# CAP_BANK.net
KiCad netlist of a schematic drawn in Altium Designer
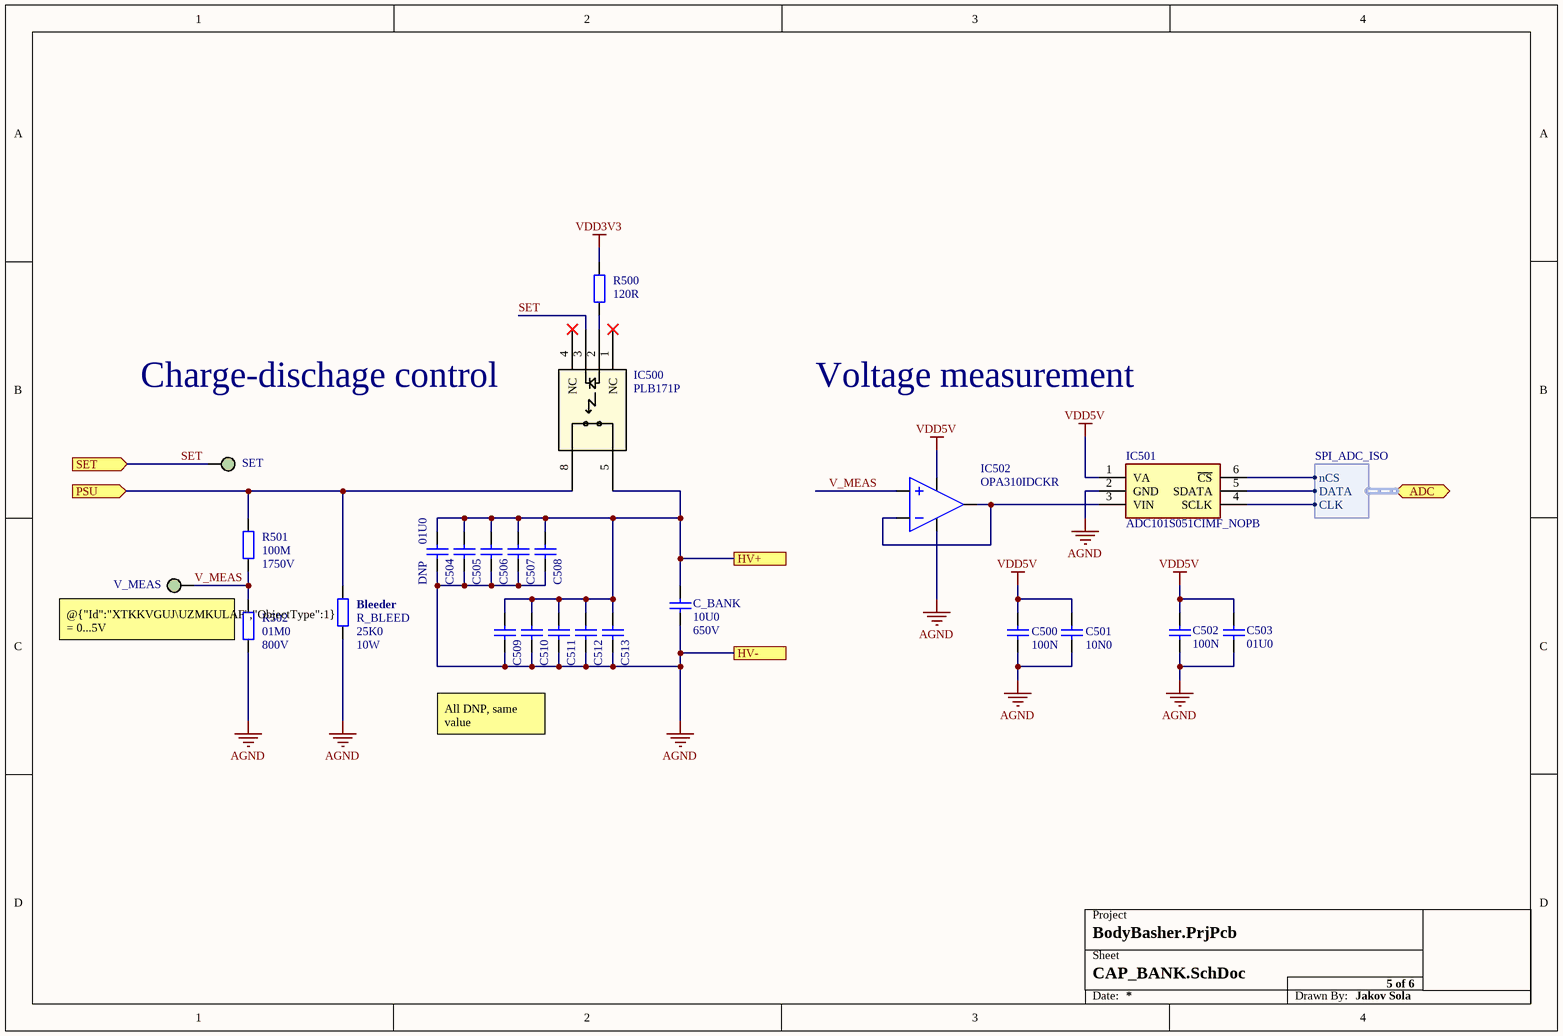
[diagram p0: CAP_BANK.SchDoc]

(export (version "E")
  (design (tool "Eeschema 10.0.6"))
  (components
    (comp (ref "C500")
      (value "Cap")
      (footprint "CAPC0603N")
      (fields
        (field (name "VALUE_4C") "100N")
        (field (name "VOLTAGE") "25V")
        (field (name "TOLERANCE") "0.1")
      )
      (libsource (lib "Capacitors") (part "Cap"))
    )
    (comp (ref "C501")
      (value "Cap")
      (footprint "CAPC0603N")
      (fields
        (field (name "VALUE_4C") "10N0")
        (field (name "VOLTAGE") "10V")
        (field (name "TOLERANCE") "0.1")
      )
      (libsource (lib "Capacitors") (part "Cap"))
    )
    (comp (ref "C502")
      (value "Cap")
      (footprint "CAPC0603N")
      (fields
        (field (name "VALUE_4C") "100N")
        (field (name "VOLTAGE") "25V")
        (field (name "TOLERANCE") "0.1")
      )
      (libsource (lib "Capacitors") (part "Cap"))
    )
    (comp (ref "C503")
      (value "Cap")
      (footprint "CAPC0603N")
      (fields
        (field (name "VALUE_4C") "01U0")
        (field (name "VOLTAGE") "25V")
        (field (name "TOLERANCE") "0.1")
      )
      (libsource (lib "Capacitors") (part "Cap"))
    )
    (comp (ref "C504")
      (value "Cap")
      (footprint "CAPC2220N")
      (fields
        (field (name "POPULATE") "DNP")
        (field (name "VALUE_4C") "01U0")
        (field (name "VOLTAGE") "600V")
        (field (name "TOLERANCE") "0.1")
      )
      (libsource (lib "Capacitors") (part "Cap"))
    )
    (comp (ref "C505")
      (value "Cap")
      (footprint "CAPC2220N")
      (fields (field (name "VOLTAGE") "600V") (field (name "TOLERANCE") "0.1"))
      (libsource (lib "Capacitors") (part "Cap"))
    )
    (comp (ref "C506")
      (value "Cap")
      (footprint "CAPC2220N")
      (fields (field (name "VOLTAGE") "600V") (field (name "TOLERANCE") "0.1"))
      (libsource (lib "Capacitors") (part "Cap"))
    )
    (comp (ref "C507")
      (value "Cap")
      (footprint "CAPC2220N")
      (fields (field (name "VOLTAGE") "600V") (field (name "TOLERANCE") "0.1"))
      (libsource (lib "Capacitors") (part "Cap"))
    )
    (comp (ref "C508")
      (value "Cap")
      (footprint "CAPC2220N")
      (fields (field (name "VOLTAGE") "600V") (field (name "TOLERANCE") "0.1"))
      (libsource (lib "Capacitors") (part "Cap"))
    )
    (comp (ref "C509")
      (value "Cap")
      (footprint "CAPC2220N")
      (fields (field (name "VOLTAGE") "600V") (field (name "TOLERANCE") "0.1"))
      (libsource (lib "Capacitors") (part "Cap"))
    )
    (comp (ref "C510")
      (value "Cap")
      (footprint "CAPC2220N")
      (fields (field (name "VOLTAGE") "600V") (field (name "TOLERANCE") "0.1"))
      (libsource (lib "Capacitors") (part "Cap"))
    )
    (comp (ref "C511")
      (value "Cap")
      (footprint "CAPC2220N")
      (fields (field (name "VOLTAGE") "600V") (field (name "TOLERANCE") "0.1"))
      (libsource (lib "Capacitors") (part "Cap"))
    )
    (comp (ref "C512")
      (value "Cap")
      (footprint "CAPC2220N")
      (fields (field (name "VOLTAGE") "600V") (field (name "TOLERANCE") "0.1"))
      (libsource (lib "Capacitors") (part "Cap"))
    )
    (comp (ref "C513")
      (value "Cap")
      (footprint "CAPC2220N")
      (fields (field (name "VOLTAGE") "600V") (field (name "TOLERANCE") "0.1"))
      (libsource (lib "Capacitors") (part "Cap"))
    )
    (comp (ref "C_BANK")
      (value "Cap")
      (footprint "CAP_TH_15MM_RADIAL_30X58MM")
      (fields
        (field (name "VALUE_4C") "10U0")
        (field (name "VOLTAGE") "650V")
        (field (name "TOLERANCE") "0.1")
      )
      (libsource (lib "Capacitors") (part "Cap"))
    )
    (comp (ref "IC500")
      (value "SSR_SPST_NC")
      (footprint "PLB171P")
      (description "Solid State SPST-NC (1 Form B) 8-SMD (0.300\", 7.62mm), 6 Leads")
      (fields (field (name "MANUFCODE") "PLB171P"))
      (libsource (lib "Integrated_circuits") (part "SSR_SPST_NC"))
    )
    (comp (ref "IC501")
      (value "ADC101S051CIMF_NOPB")
      (footprint "SOT95P280X145-6N")
      (libsource (lib "Integrated_circuits") (part "ADC101S051CIMF_NOPB"))
    )
    (comp (ref "IC502")
      (value "OPA310IDCKR")
      (footprint "SOT65P210X110-5N")
      (libsource (lib "Integrated_circuits") (part "OPA310IDCKR"))
    )
    (comp (ref "R500")
      (value "Res")
      (footprint "RESC0603N")
      (description "Resistor")
      (fields (field (name "VALUE_4C") "120R") (field (name "POWER") "0.1W") (field (name "TOLERANCE") "1%"))
      (libsource (lib "Resistors") (part "Res"))
    )
    (comp (ref "R501")
      (value "Res")
      (footprint "RESC1210N")
      (description "Resistor")
      (fields
        (field (name "VALUE_4C") "100M")
        (field (name "POWER") "0.45W")
        (field (name "TOLERANCE") "1%")
        (field (name "VOLTAGE") "1750V")
      )
      (libsource (lib "Resistors") (part "Res"))
    )
    (comp (ref "R502")
      (value "Res")
      (footprint "RESC1210N")
      (description "Resistor")
      (fields
        (field (name "VALUE_4C") "01M0")
        (field (name "POWER") "0.25W")
        (field (name "TOLERANCE") "1%")
        (field (name "VOLTAGE") "800V")
      )
      (libsource (lib "Resistors") (part "Res"))
    )
    (comp (ref "R_BLEED")
      (value "Res")
      (footprint "RESAD8333W107L4521D953")
      (description "Resistor")
      (fields (field (name "VALUE_4C") "25K0") (field (name "POWER") "10W") (field (name "TOLERANCE") "1%"))
      (libsource (lib "Resistors") (part "Res"))
    )
    (comp (ref "SET") (value "TP") (footprint "TP") (libsource (lib "Other_passive") (part "TP")))
    (comp (ref "V_MEAS") (value "TP") (footprint "TP") (libsource (lib "Other_passive") (part "TP")))
  )
  (nets
    (net (code "2") (name "/CLK") (class "Default")
      (node (ref "IC501") (pin "4") (pinfunction "SCLK_4") (pintype "passive"))
    )
    (net (code "3") (name "/DATA") (class "Default")
      (node (ref "IC501") (pin "5") (pinfunction "SDATA_5") (pintype "passive"))
    )
    (net (code "4") (name "/HV+") (class "Default")
      (node (ref "C504") (pin "2") (pinfunction "2_2") (pintype "passive"))
      (node (ref "C505") (pin "2") (pinfunction "2_2") (pintype "passive"))
      (node (ref "C506") (pin "2") (pinfunction "2_2") (pintype "passive"))
      (node (ref "C507") (pin "2") (pinfunction "2_2") (pintype "passive"))
      (node (ref "C508") (pin "2") (pinfunction "2_2") (pintype "passive"))
      (node (ref "C509") (pin "2") (pinfunction "2_2") (pintype "passive"))
      (node (ref "C510") (pin "2") (pinfunction "2_2") (pintype "passive"))
      (node (ref "C511") (pin "2") (pinfunction "2_2") (pintype "passive"))
      (node (ref "C512") (pin "2") (pinfunction "2_2") (pintype "passive"))
      (node (ref "C513") (pin "2") (pinfunction "2_2") (pintype "passive"))
      (node (ref "C_BANK") (pin "2") (pinfunction "2_2") (pintype "passive"))
      (node (ref "IC500") (pin "5") (pinfunction "NOCL1_5") (pintype "passive"))
    )
    (net (code "5") (name "/PSU") (class "Default")
      (node (ref "IC500") (pin "8") (pinfunction "NOOP2_8") (pintype "passive"))
      (node (ref "R501") (pin "2") (pinfunction "2_2") (pintype "passive"))
      (node (ref "R_BLEED") (pin "2") (pinfunction "2_2") (pintype "passive"))
    )
    (net (code "6") (name "/SET") (class "Default")
      (node (ref "IC500") (pin "3") (pinfunction "-_3") (pintype "passive"))
      (node (ref "SET") (pin "TP") (pinfunction "TP_TP") (pintype "passive"))
    )
    (net (code "7") (name "/V_MEAS") (class "Default")
      (node (ref "IC502") (pin "1") (pinfunction "IN+_1") (pintype "passive"))
      (node (ref "R501") (pin "1") (pinfunction "1_1") (pintype "passive"))
      (node (ref "R502") (pin "2") (pinfunction "2_2") (pintype "passive"))
      (node (ref "V_MEAS") (pin "TP") (pinfunction "TP_TP") (pintype "passive"))
    )
    (net (code "8") (name "/nCS") (class "Default")
      (node (ref "IC501") (pin "6") (pinfunction "~{CS}_6") (pintype "passive"))
    )
    (net (code "10") (name "AGND") (class "Default")
      (node (ref "C500") (pin "2") (pinfunction "2_2") (pintype "passive"))
      (node (ref "C501") (pin "1") (pinfunction "1_1") (pintype "passive"))
      (node (ref "C502") (pin "2") (pinfunction "2_2") (pintype "passive"))
      (node (ref "C503") (pin "1") (pinfunction "1_1") (pintype "passive"))
      (node (ref "C504") (pin "1") (pinfunction "1_1") (pintype "passive"))
      (node (ref "C505") (pin "1") (pinfunction "1_1") (pintype "passive"))
      (node (ref "C506") (pin "1") (pinfunction "1_1") (pintype "passive"))
      (node (ref "C507") (pin "1") (pinfunction "1_1") (pintype "passive"))
      (node (ref "C508") (pin "1") (pinfunction "1_1") (pintype "passive"))
      (node (ref "C509") (pin "1") (pinfunction "1_1") (pintype "passive"))
      (node (ref "C510") (pin "1") (pinfunction "1_1") (pintype "passive"))
      (node (ref "C511") (pin "1") (pinfunction "1_1") (pintype "passive"))
      (node (ref "C512") (pin "1") (pinfunction "1_1") (pintype "passive"))
      (node (ref "C513") (pin "1") (pinfunction "1_1") (pintype "passive"))
      (node (ref "C_BANK") (pin "1") (pinfunction "1_1") (pintype "passive"))
      (node (ref "IC501") (pin "2") (pinfunction "GND_2") (pintype "passive"))
      (node (ref "IC502") (pin "2") (pinfunction "V-_2") (pintype "passive"))
      (node (ref "R502") (pin "1") (pinfunction "1_1") (pintype "passive"))
      (node (ref "R_BLEED") (pin "1") (pinfunction "1_1") (pintype "passive"))
    )
    (net (code "11") (name "Net-(IC500-+)") (class "Default")
      (node (ref "IC500") (pin "2") (pinfunction "+_2") (pintype "passive"))
      (node (ref "R500") (pin "1") (pinfunction "1_1") (pintype "passive"))
    )
    (net (code "12") (name "Net-(IC501-VIN)") (class "Default")
      (node (ref "IC501") (pin "3") (pinfunction "VIN_3") (pintype "passive"))
      (node (ref "IC502") (pin "3") (pinfunction "IN-_3") (pintype "passive"))
      (node (ref "IC502") (pin "4") (pinfunction "OUT_4") (pintype "passive"))
    )
    (net (code "13") (name "VDD3V3") (class "Default")
      (node (ref "R500") (pin "2") (pinfunction "2_2") (pintype "passive"))
    )
    (net (code "14") (name "VDD5V") (class "Default")
      (node (ref "C500") (pin "1") (pinfunction "1_1") (pintype "passive"))
      (node (ref "C501") (pin "2") (pinfunction "2_2") (pintype "passive"))
      (node (ref "C502") (pin "1") (pinfunction "1_1") (pintype "passive"))
      (node (ref "C503") (pin "2") (pinfunction "2_2") (pintype "passive"))
      (node (ref "IC501") (pin "1") (pinfunction "VA_1") (pintype "passive"))
      (node (ref "IC502") (pin "5") (pinfunction "V+_5") (pintype "passive"))
    )
    (net (code "15") (name "unconnected-(IC500-NC-Pad1)") (class "Default")
      (node (ref "IC500") (pin "1") (pinfunction "NC_1") (pintype "passive+no_connect"))
    )
    (net (code "16") (name "unconnected-(IC500-NC-Pad4)") (class "Default")
      (node (ref "IC500") (pin "4") (pinfunction "NC_4") (pintype "passive+no_connect"))
    )
  )
)
